# 01_GAP_POWER.net
KiCad netlist of a schematic drawn in Altium Designer
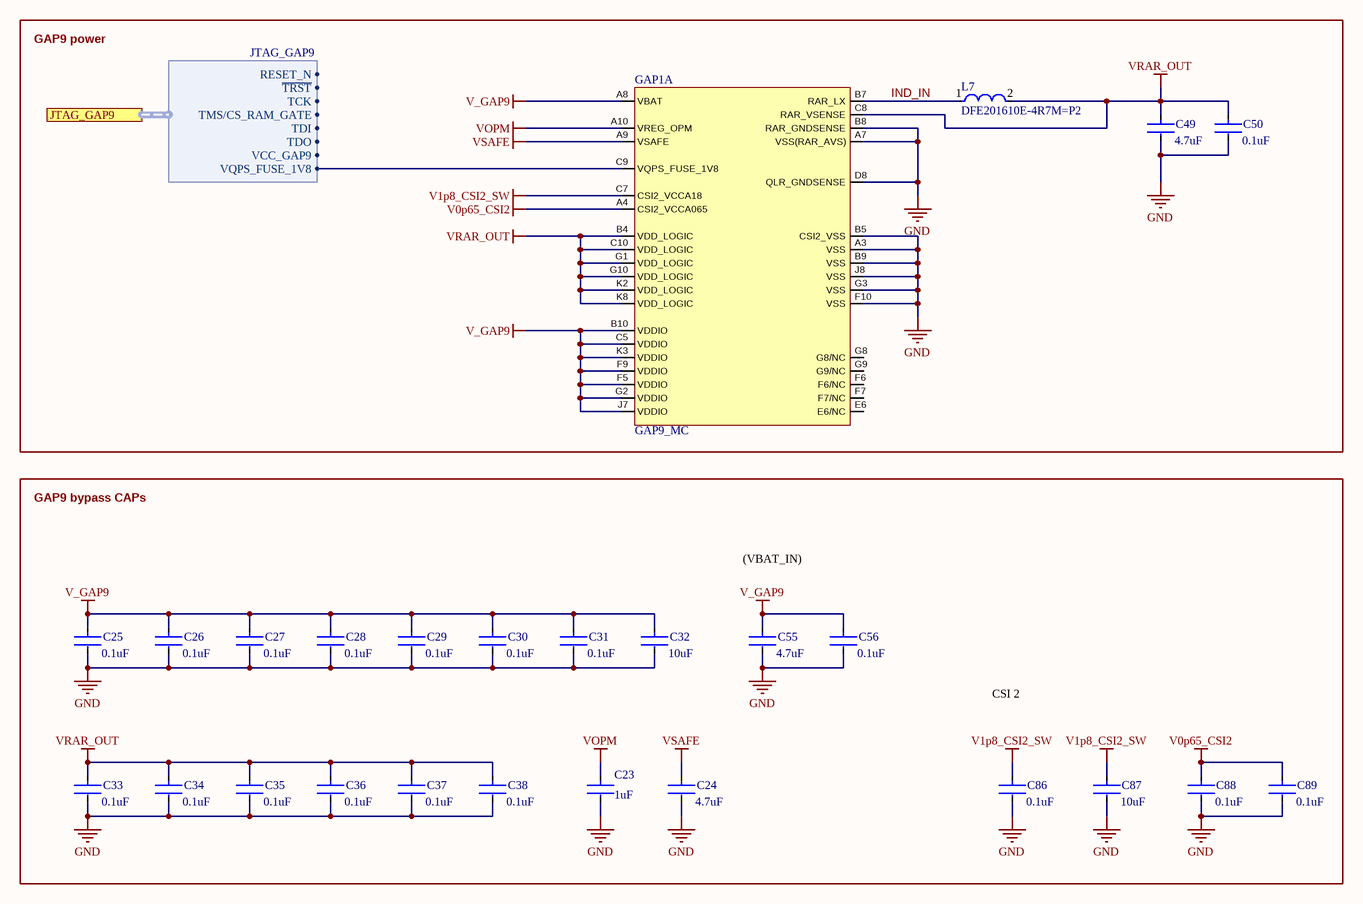
[diagram p0: 01_GAP_POWER.SchDoc]

(export (version "E")
  (design (tool "Eeschema 10.0.6"))
  (components
    (comp (ref "C23")
      (value "CL03A105KP3NSNC")
      (footprint "FP-CL03-IPC_B")
      (description "Cap Ceramic 1uF 10V X5R ±10% Pad SMD 0201 +85°C T/R")
      (fields (field (name "TOLERANCE") "10%") (field (name "CAPACITANCE") "1uF"))
      (libsource (lib "Altium Content Vault") (part "b4654b650e69147ec39a6b967a45e02"))
    )
    (comp (ref "C24")
      (value "C1005X5R0J475K050BC")
      (footprint "FP-C1005-050-0_15-IPC_B")
      (description "CAP CER 4.7UF 6.3V X5R 0402")
      (fields
        (field (name "VOLTAGE") "6.3V")
        (field (name "CAPACITANCE") "4.7uF")
        (field (name "TOLERANCE") "10%")
      )
      (libsource (lib "Altium Content Vault") (part "02cd4be3c70576c341d710602a673aa"))
    )
    (comp (ref "C25")
      (value "GRM033Z71C104KE14D")
      (footprint "FP-GRM033-0_03-IPC_B")
      (description "Chip Multilayer Ceramic Capacitors for General Purpose, 0201, 0.10uF, X7R, 15%, 10%, 16V")
      (fields (field (name "CAPACITANCE") "0.1uF"))
      (libsource (lib "Altium Content Vault") (part "b4654b650e69147ec39a6b967a45e02"))
    )
    (comp (ref "C26")
      (value "GRM033Z71C104KE14D")
      (footprint "FP-GRM033-0_03-IPC_B")
      (description "Chip Multilayer Ceramic Capacitors for General Purpose, 0201, 0.10uF, X7R, 15%, 10%, 16V")
      (fields (field (name "CAPACITANCE") "0.1uF"))
      (libsource (lib "Altium Content Vault") (part "b4654b650e69147ec39a6b967a45e02"))
    )
    (comp (ref "C27")
      (value "GRM033Z71C104KE14D")
      (footprint "FP-GRM033-0_03-IPC_B")
      (description "Chip Multilayer Ceramic Capacitors for General Purpose, 0201, 0.10uF, X7R, 15%, 10%, 16V")
      (fields (field (name "CAPACITANCE") "0.1uF"))
      (libsource (lib "Altium Content Vault") (part "b4654b650e69147ec39a6b967a45e02"))
    )
    (comp (ref "C28")
      (value "GRM033Z71C104KE14D")
      (footprint "FP-GRM033-0_03-IPC_B")
      (description "Chip Multilayer Ceramic Capacitors for General Purpose, 0201, 0.10uF, X7R, 15%, 10%, 16V")
      (fields (field (name "CAPACITANCE") "0.1uF"))
      (libsource (lib "Altium Content Vault") (part "b4654b650e69147ec39a6b967a45e02"))
    )
    (comp (ref "C29")
      (value "GRM033Z71C104KE14D")
      (footprint "FP-GRM033-0_03-IPC_B")
      (description "Chip Multilayer Ceramic Capacitors for General Purpose, 0201, 0.10uF, X7R, 15%, 10%, 16V")
      (fields (field (name "CAPACITANCE") "0.1uF"))
      (libsource (lib "Altium Content Vault") (part "b4654b650e69147ec39a6b967a45e02"))
    )
    (comp (ref "C30")
      (value "GRM033Z71C104KE14D")
      (footprint "FP-GRM033-0_03-IPC_B")
      (description "Chip Multilayer Ceramic Capacitors for General Purpose, 0201, 0.10uF, X7R, 15%, 10%, 16V")
      (fields (field (name "CAPACITANCE") "0.1uF"))
      (libsource (lib "Altium Content Vault") (part "b4654b650e69147ec39a6b967a45e02"))
    )
    (comp (ref "C31")
      (value "GRM033Z71C104KE14D")
      (footprint "FP-GRM033-0_03-IPC_B")
      (description "Chip Multilayer Ceramic Capacitors for General Purpose, 0201, 0.10uF, X7R, 15%, 10%, 16V")
      (fields (field (name "CAPACITANCE") "0.1uF"))
      (libsource (lib "Altium Content Vault") (part "b4654b650e69147ec39a6b967a45e02"))
    )
    (comp (ref "C32")
      (value "CL05A106MP5NUNC")
      (footprint "FP-CL05A106MP5NUNC-IPC_B")
      (description "CAP CER 10UF 10V X5R 0402")
      (fields
        (field (name "OCTOPART") "https://octopart.com/cl05a106mp5nunc-samsung-22457395")
        (field (name "TOLERANCE") "20%")
        (field (name "CAPACITANCE") "10uF")
      )
      (libsource (lib "Altium Content Vault") (part "b4654b650e69147ec39a6b967a45e02"))
    )
    (comp (ref "C33")
      (value "GRM033Z71C104KE14D")
      (footprint "FP-GRM033-0_03-IPC_B")
      (description "Chip Multilayer Ceramic Capacitors for General Purpose, 0201, 0.10uF, X7R, 15%, 10%, 16V")
      (fields (field (name "CAPACITANCE") "0.1uF"))
      (libsource (lib "Altium Content Vault") (part "b4654b650e69147ec39a6b967a45e02"))
    )
    (comp (ref "C34")
      (value "GRM033Z71C104KE14D")
      (footprint "FP-GRM033-0_03-IPC_B")
      (description "Chip Multilayer Ceramic Capacitors for General Purpose, 0201, 0.10uF, X7R, 15%, 10%, 16V")
      (fields (field (name "CAPACITANCE") "0.1uF"))
      (libsource (lib "Altium Content Vault") (part "b4654b650e69147ec39a6b967a45e02"))
    )
    (comp (ref "C35")
      (value "GRM033Z71C104KE14D")
      (footprint "FP-GRM033-0_03-IPC_B")
      (description "Chip Multilayer Ceramic Capacitors for General Purpose, 0201, 0.10uF, X7R, 15%, 10%, 16V")
      (fields (field (name "CAPACITANCE") "0.1uF"))
      (libsource (lib "Altium Content Vault") (part "b4654b650e69147ec39a6b967a45e02"))
    )
    (comp (ref "C36")
      (value "GRM033Z71C104KE14D")
      (footprint "FP-GRM033-0_03-IPC_B")
      (description "Chip Multilayer Ceramic Capacitors for General Purpose, 0201, 0.10uF, X7R, 15%, 10%, 16V")
      (fields (field (name "CAPACITANCE") "0.1uF"))
      (libsource (lib "Altium Content Vault") (part "b4654b650e69147ec39a6b967a45e02"))
    )
    (comp (ref "C37")
      (value "GRM033Z71C104KE14D")
      (footprint "FP-GRM033-0_03-IPC_B")
      (description "Chip Multilayer Ceramic Capacitors for General Purpose, 0201, 0.10uF, X7R, 15%, 10%, 16V")
      (fields (field (name "CAPACITANCE") "0.1uF"))
      (libsource (lib "Altium Content Vault") (part "b4654b650e69147ec39a6b967a45e02"))
    )
    (comp (ref "C38")
      (value "GRM033Z71C104KE14D")
      (footprint "FP-GRM033-0_03-IPC_B")
      (description "Chip Multilayer Ceramic Capacitors for General Purpose, 0201, 0.10uF, X7R, 15%, 10%, 16V")
      (fields (field (name "CAPACITANCE") "0.1uF"))
      (libsource (lib "Altium Content Vault") (part "b4654b650e69147ec39a6b967a45e02"))
    )
    (comp (ref "C49")
      (value "C1005X5R0J475K050BC")
      (footprint "FP-C1005-050-0_15-IPC_B")
      (description "CAP CER 4.7UF 6.3V X5R 0402")
      (fields
        (field (name "VOLTAGE") "6.3V")
        (field (name "CAPACITANCE") "4.7uF")
        (field (name "TOLERANCE") "10%")
      )
      (libsource (lib "Altium Content Vault") (part "02cd4be3c70576c341d710602a673aa"))
    )
    (comp (ref "C50")
      (value "GRM033Z71C104KE14D")
      (footprint "FP-GRM033-0_03-IPC_B")
      (description "Chip Multilayer Ceramic Capacitors for General Purpose, 0201, 0.10uF, X7R, 15%, 10%, 16V")
      (fields (field (name "CAPACITANCE") "0.1uF"))
      (libsource (lib "Altium Content Vault") (part "b4654b650e69147ec39a6b967a45e02"))
    )
    (comp (ref "C55")
      (value "C1005X5R0J475K050BC")
      (footprint "FP-C1005-050-0_15-IPC_B")
      (description "CAP CER 4.7UF 6.3V X5R 0402")
      (fields
        (field (name "VOLTAGE") "6.3V")
        (field (name "CAPACITANCE") "4.7uF")
        (field (name "TOLERANCE") "10%")
      )
      (libsource (lib "Altium Content Vault") (part "02cd4be3c70576c341d710602a673aa"))
    )
    (comp (ref "C56")
      (value "GRM033Z71C104KE14D")
      (footprint "FP-GRM033-0_03-IPC_B")
      (description "Chip Multilayer Ceramic Capacitors for General Purpose, 0201, 0.10uF, X7R, 15%, 10%, 16V")
      (fields (field (name "CAPACITANCE") "0.1uF"))
      (libsource (lib "Altium Content Vault") (part "b4654b650e69147ec39a6b967a45e02"))
    )
    (comp (ref "C86")
      (value "GRM033Z71C104KE14D")
      (footprint "FP-GRM033-0_03-IPC_B")
      (description "Chip Multilayer Ceramic Capacitors for General Purpose, 0201, 0.10uF, X7R, 15%, 10%, 16V")
      (fields (field (name "CAPACITANCE") "0.1uF"))
      (libsource (lib "Altium Content Vault") (part "b4654b650e69147ec39a6b967a45e02"))
    )
    (comp (ref "C87")
      (value "CL05A106MP5NUNC")
      (footprint "FP-CL05A106MP5NUNC-IPC_B")
      (description "CAP CER 10UF 10V X5R 0402")
      (fields
        (field (name "OCTOPART") "https://octopart.com/cl05a106mp5nunc-samsung-22457395")
        (field (name "TOLERANCE") "20%")
        (field (name "CAPACITANCE") "10uF")
      )
      (libsource (lib "Altium Content Vault") (part "b4654b650e69147ec39a6b967a45e02"))
    )
    (comp (ref "C88")
      (value "GRM033Z71C104KE14D")
      (footprint "FP-GRM033-0_03-IPC_B")
      (description "Chip Multilayer Ceramic Capacitors for General Purpose, 0201, 0.10uF, X7R, 15%, 10%, 16V")
      (fields (field (name "CAPACITANCE") "0.1uF"))
      (libsource (lib "Altium Content Vault") (part "b4654b650e69147ec39a6b967a45e02"))
    )
    (comp (ref "C89")
      (value "GRM033Z71C104KE14D")
      (footprint "FP-GRM033-0_03-IPC_B")
      (description "Chip Multilayer Ceramic Capacitors for General Purpose, 0201, 0.10uF, X7R, 15%, 10%, 16V")
      (fields (field (name "CAPACITANCE") "0.1uF"))
      (libsource (lib "Altium Content Vault") (part "b4654b650e69147ec39a6b967a45e02"))
    )
    (comp (ref "GAP1")
      (value "GAP9_MC")
      (footprint "EEG_PcbLib:GAP9")
      (libsource (lib "EEG_SchLib") (part "GAP9_MC"))
    )
    (comp (ref "L7")
      (value "DFE201610E-4R7M=P2")
      (footprint "FP-DFE201610C-MFG")
      (description "Shielded Wirewound Inductor 4.7uH 20% 1100mA 0.288Ω 0806 (2016)")
      (libsource (lib "Altium Content Vault") (part "725321dda6339637d4d059423bc1c3c"))
    )
  )
  (nets
    (net (code "2") (name "/IND_IN") (class "Default")
      (node (ref "GAP1") (pin "B7") (pinfunction "RAR_LX_B7") (pintype "passive"))
      (node (ref "L7") (pin "1") (pinfunction "1_1") (pintype "passive"))
    )
    (net (code "3") (name "/VQPS_FUSE_1V8") (class "Default")
      (node (ref "GAP1") (pin "C9") (pinfunction "VQPS_FUSE_1V8_C9") (pintype "passive"))
    )
    (net (code "5") (name "GND") (class "Default")
      (node (ref "C23") (pin "2") (pinfunction "2_2") (pintype "passive"))
      (node (ref "C24") (pin "2") (pinfunction "2_2") (pintype "passive"))
      (node (ref "C25") (pin "2") (pinfunction "2_2") (pintype "passive"))
      (node (ref "C26") (pin "2") (pinfunction "2_2") (pintype "passive"))
      (node (ref "C27") (pin "2") (pinfunction "2_2") (pintype "passive"))
      (node (ref "C28") (pin "2") (pinfunction "2_2") (pintype "passive"))
      (node (ref "C29") (pin "2") (pinfunction "2_2") (pintype "passive"))
      (node (ref "C30") (pin "2") (pinfunction "2_2") (pintype "passive"))
      (node (ref "C31") (pin "2") (pinfunction "2_2") (pintype "passive"))
      (node (ref "C32") (pin "2") (pinfunction "2_2") (pintype "passive"))
      (node (ref "C33") (pin "2") (pinfunction "2_2") (pintype "passive"))
      (node (ref "C34") (pin "2") (pinfunction "2_2") (pintype "passive"))
      (node (ref "C35") (pin "2") (pinfunction "2_2") (pintype "passive"))
      (node (ref "C36") (pin "2") (pinfunction "2_2") (pintype "passive"))
      (node (ref "C37") (pin "2") (pinfunction "2_2") (pintype "passive"))
      (node (ref "C38") (pin "2") (pinfunction "2_2") (pintype "passive"))
      (node (ref "C49") (pin "2") (pinfunction "2_2") (pintype "passive"))
      (node (ref "C50") (pin "2") (pinfunction "2_2") (pintype "passive"))
      (node (ref "C55") (pin "2") (pinfunction "2_2") (pintype "passive"))
      (node (ref "C56") (pin "2") (pinfunction "2_2") (pintype "passive"))
      (node (ref "C86") (pin "2") (pinfunction "2_2") (pintype "passive"))
      (node (ref "C87") (pin "2") (pinfunction "2_2") (pintype "passive"))
      (node (ref "C88") (pin "2") (pinfunction "2_2") (pintype "passive"))
      (node (ref "C89") (pin "2") (pinfunction "2_2") (pintype "passive"))
      (node (ref "GAP1") (pin "A3") (pinfunction "VSS_A3") (pintype "passive"))
      (node (ref "GAP1") (pin "A7") (pinfunction "VSS(RAR_AVS)_A7") (pintype "passive"))
      (node (ref "GAP1") (pin "B5") (pinfunction "CSI2_VSS_B5") (pintype "passive"))
      (node (ref "GAP1") (pin "B8") (pinfunction "RAR_GNDSENSE_B8") (pintype "passive"))
      (node (ref "GAP1") (pin "B9") (pinfunction "VSS_B9") (pintype "passive"))
      (node (ref "GAP1") (pin "D8") (pinfunction "QLR_GNDSENSE_D8") (pintype "passive"))
      (node (ref "GAP1") (pin "F10") (pinfunction "VSS_F10") (pintype "passive"))
      (node (ref "GAP1") (pin "G3") (pinfunction "VSS_G3") (pintype "passive"))
      (node (ref "GAP1") (pin "J8") (pinfunction "VSS_J8") (pintype "passive"))
    )
    (net (code "6") (name "V0p65_CSI2") (class "Default")
      (node (ref "C88") (pin "1") (pinfunction "1_1") (pintype "passive"))
      (node (ref "C89") (pin "1") (pinfunction "1_1") (pintype "passive"))
      (node (ref "GAP1") (pin "A4") (pinfunction "CSI2_VCCA065_A4") (pintype "passive"))
    )
    (net (code "7") (name "V1p8_CSI2_SW") (class "Default")
      (node (ref "C86") (pin "1") (pinfunction "1_1") (pintype "passive"))
      (node (ref "C87") (pin "1") (pinfunction "1_1") (pintype "passive"))
      (node (ref "GAP1") (pin "C7") (pinfunction "CSI2_VCCA18_C7") (pintype "passive"))
    )
    (net (code "8") (name "VOPM") (class "Default")
      (node (ref "C23") (pin "1") (pinfunction "1_1") (pintype "passive"))
      (node (ref "GAP1") (pin "A10") (pinfunction "VREG_OPM_A10") (pintype "passive"))
    )
    (net (code "9") (name "VRAR_OUT") (class "Default")
      (node (ref "C33") (pin "1") (pinfunction "1_1") (pintype "passive"))
      (node (ref "C34") (pin "1") (pinfunction "1_1") (pintype "passive"))
      (node (ref "C35") (pin "1") (pinfunction "1_1") (pintype "passive"))
      (node (ref "C36") (pin "1") (pinfunction "1_1") (pintype "passive"))
      (node (ref "C37") (pin "1") (pinfunction "1_1") (pintype "passive"))
      (node (ref "C38") (pin "1") (pinfunction "1_1") (pintype "passive"))
      (node (ref "C49") (pin "1") (pinfunction "1_1") (pintype "passive"))
      (node (ref "C50") (pin "1") (pinfunction "1_1") (pintype "passive"))
      (node (ref "GAP1") (pin "B4") (pinfunction "VDD_LOGIC_B4") (pintype "passive"))
      (node (ref "GAP1") (pin "C10") (pinfunction "VDD_LOGIC_C10") (pintype "passive"))
      (node (ref "GAP1") (pin "C8") (pinfunction "RAR_VSENSE_C8") (pintype "passive"))
      (node (ref "GAP1") (pin "G1") (pinfunction "VDD_LOGIC_G1") (pintype "passive"))
      (node (ref "GAP1") (pin "G10") (pinfunction "VDD_LOGIC_G10") (pintype "passive"))
      (node (ref "GAP1") (pin "K2") (pinfunction "VDD_LOGIC_K2") (pintype "passive"))
      (node (ref "GAP1") (pin "K8") (pinfunction "VDD_LOGIC_K8") (pintype "passive"))
      (node (ref "L7") (pin "2") (pinfunction "2_2") (pintype "passive"))
    )
    (net (code "10") (name "VSAFE") (class "Default")
      (node (ref "C24") (pin "1") (pinfunction "1_1") (pintype "passive"))
      (node (ref "GAP1") (pin "A9") (pinfunction "VSAFE_A9") (pintype "passive"))
    )
    (net (code "11") (name "V_GAP9") (class "Default")
      (node (ref "C25") (pin "1") (pinfunction "1_1") (pintype "passive"))
      (node (ref "C26") (pin "1") (pinfunction "1_1") (pintype "passive"))
      (node (ref "C27") (pin "1") (pinfunction "1_1") (pintype "passive"))
      (node (ref "C28") (pin "1") (pinfunction "1_1") (pintype "passive"))
      (node (ref "C29") (pin "1") (pinfunction "1_1") (pintype "passive"))
      (node (ref "C30") (pin "1") (pinfunction "1_1") (pintype "passive"))
      (node (ref "C31") (pin "1") (pinfunction "1_1") (pintype "passive"))
      (node (ref "C32") (pin "1") (pinfunction "1_1") (pintype "passive"))
      (node (ref "C55") (pin "1") (pinfunction "1_1") (pintype "passive"))
      (node (ref "C56") (pin "1") (pinfunction "1_1") (pintype "passive"))
      (node (ref "GAP1") (pin "A8") (pinfunction "VBAT_A8") (pintype "passive"))
      (node (ref "GAP1") (pin "B10") (pinfunction "VDDIO_B10") (pintype "passive"))
      (node (ref "GAP1") (pin "C5") (pinfunction "VDDIO_C5") (pintype "passive"))
      (node (ref "GAP1") (pin "F5") (pinfunction "VDDIO_F5") (pintype "passive"))
      (node (ref "GAP1") (pin "F9") (pinfunction "VDDIO_F9") (pintype "passive"))
      (node (ref "GAP1") (pin "G2") (pinfunction "VDDIO_G2") (pintype "passive"))
      (node (ref "GAP1") (pin "J7") (pinfunction "VDDIO_J7") (pintype "passive"))
      (node (ref "GAP1") (pin "K3") (pinfunction "VDDIO_K3") (pintype "passive"))
    )
    (net (code "12") (name "unconnected-(GAP1A-E6{slash}NC-PadE6)") (class "Default")
      (node (ref "GAP1") (pin "E6") (pinfunction "E6/NC_E6") (pintype "passive"))
    )
    (net (code "13") (name "unconnected-(GAP1A-F6{slash}NC-PadF6)") (class "Default")
      (node (ref "GAP1") (pin "F6") (pinfunction "F6/NC_F6") (pintype "passive"))
    )
    (net (code "14") (name "unconnected-(GAP1A-F7{slash}NC-PadF7)") (class "Default")
      (node (ref "GAP1") (pin "F7") (pinfunction "F7/NC_F7") (pintype "passive"))
    )
    (net (code "15") (name "unconnected-(GAP1A-G8{slash}NC-PadG8)") (class "Default")
      (node (ref "GAP1") (pin "G8") (pinfunction "G8/NC_G8") (pintype "passive"))
    )
    (net (code "16") (name "unconnected-(GAP1A-G9{slash}NC-PadG9)") (class "Default")
      (node (ref "GAP1") (pin "G9") (pinfunction "G9/NC_G9") (pintype "passive"))
    )
  )
)
